# Adapter-TenX-CurrentSink.net
KiCad netlist of a schematic drawn in EAGLE
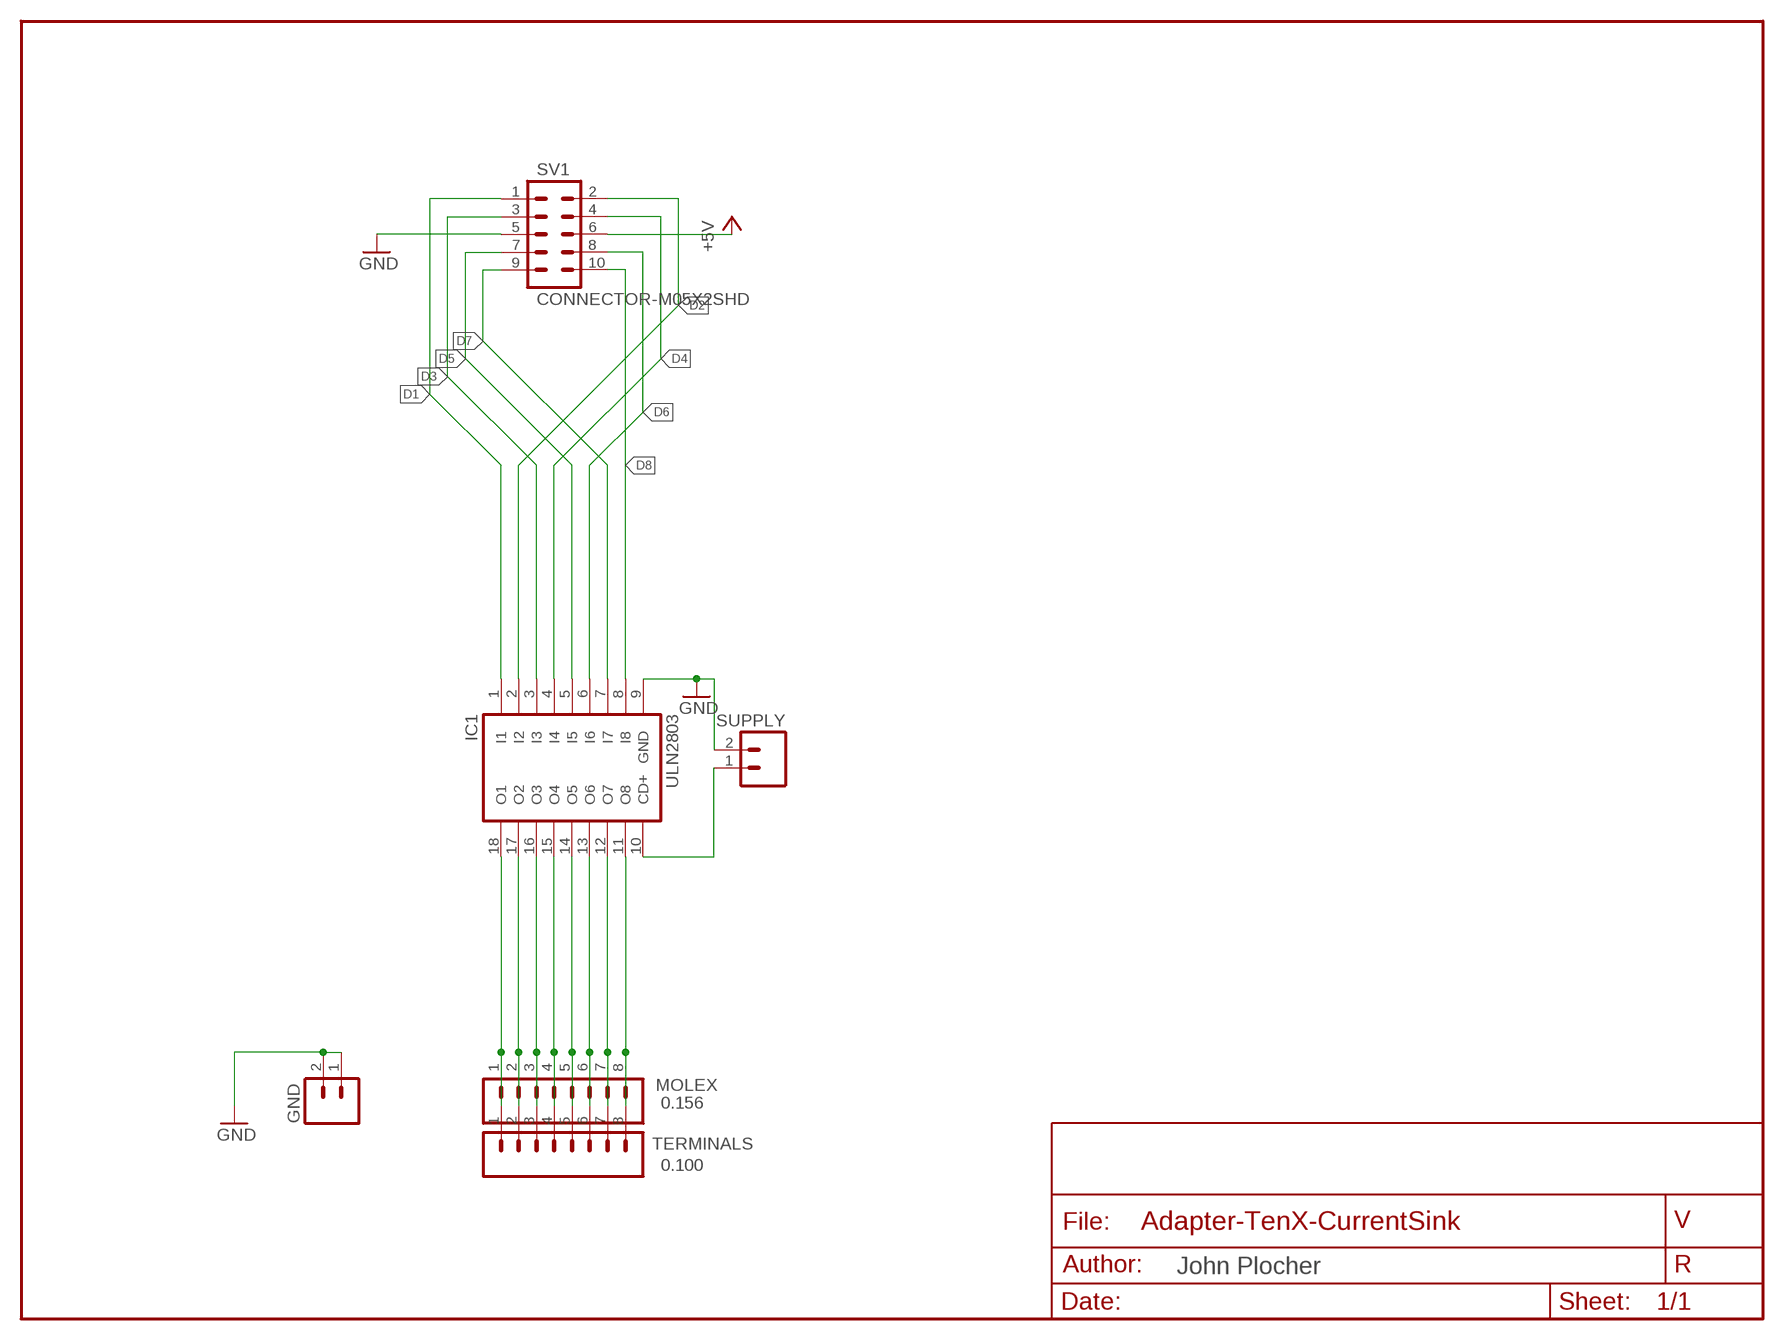
[diagram p0: schematic, sheet 1]

(export (version "E")
  (design (tool "Eeschema 10.0.6"))
  (components
    (comp (ref "GND")
      (value "M02POLAR_LOCK")
      (footprint "eagle-import:MOLEX-1X2_LOCK")
      (libsource (lib "eagle-import") (part "M02POLAR_LOCK"))
    )
    (comp (ref "IC1")
      (value "ULN2803")
      (footprint "eagle-import:DIL18")
      (libsource (lib "eagle-import") (part "ULN2803A"))
    )
    (comp (ref "MOLEX")
      (value "0.156")
      (footprint "eagle-import:KK-156-8-M")
      (libsource (lib "eagle-import") (part "CONNECTOR-M081.56-M"))
    )
    (comp (ref "SUPPLY")
      (value "M02POLAR_LOCK")
      (footprint "eagle-import:MOLEX-1X2_LOCK")
      (libsource (lib "eagle-import") (part "M02POLAR_LOCK"))
    )
    (comp (ref "SV1")
      (value "CONNECTOR-M05X2SHD")
      (footprint "eagle-import:2X5-SHROUDED")
      (libsource (lib "eagle-import") (part "CONNECTOR-M05X2SHD"))
    )
    (comp (ref "TERMINALS")
      (value "0.100")
      (footprint "eagle-import:1X08_LOCK_LONGPADS")
      (libsource (lib "eagle-import") (part "CONNECTOR-M08LOCK_LONGPADS"))
    )
  )
  (nets
    (net (code "1") (name "+5V") (class "Default")
      (node (ref "SV1") (pin "6") (pinfunction "6_6") (pintype "passive"))
    )
    (net (code "2") (name "D1") (class "Default")
      (node (ref "IC1") (pin "1") (pinfunction "I1_1") (pintype "input"))
      (node (ref "SV1") (pin "1") (pinfunction "1_1") (pintype "passive"))
    )
    (net (code "3") (name "D2") (class "Default")
      (node (ref "IC1") (pin "2") (pinfunction "I2_2") (pintype "input"))
      (node (ref "SV1") (pin "2") (pinfunction "2_2") (pintype "passive"))
    )
    (net (code "4") (name "D3") (class "Default")
      (node (ref "IC1") (pin "3") (pinfunction "I3_3") (pintype "input"))
      (node (ref "SV1") (pin "3") (pinfunction "3_3") (pintype "passive"))
    )
    (net (code "5") (name "D4") (class "Default")
      (node (ref "IC1") (pin "4") (pinfunction "I4_4") (pintype "input"))
      (node (ref "SV1") (pin "4") (pinfunction "4_4") (pintype "passive"))
    )
    (net (code "6") (name "D5") (class "Default")
      (node (ref "IC1") (pin "5") (pinfunction "I5_5") (pintype "input"))
      (node (ref "SV1") (pin "7") (pinfunction "7_7") (pintype "passive"))
    )
    (net (code "7") (name "D6") (class "Default")
      (node (ref "IC1") (pin "6") (pinfunction "I6_6") (pintype "input"))
      (node (ref "SV1") (pin "8") (pinfunction "8_8") (pintype "passive"))
    )
    (net (code "8") (name "D7") (class "Default")
      (node (ref "IC1") (pin "7") (pinfunction "I7_7") (pintype "input"))
      (node (ref "SV1") (pin "9") (pinfunction "9_9") (pintype "passive"))
    )
    (net (code "9") (name "D8") (class "Default")
      (node (ref "IC1") (pin "8") (pinfunction "I8_8") (pintype "input"))
      (node (ref "SV1") (pin "10") (pinfunction "10_10") (pintype "passive"))
    )
    (net (code "10") (name "GND") (class "Default")
      (node (ref "GND") (pin "1") (pinfunction "1_1") (pintype "passive"))
      (node (ref "GND") (pin "2") (pinfunction "2_2") (pintype "passive"))
      (node (ref "IC1") (pin "9") (pinfunction "GND_9") (pintype "power_in"))
      (node (ref "SUPPLY") (pin "2") (pinfunction "2_2") (pintype "passive"))
      (node (ref "SV1") (pin "5") (pinfunction "5_5") (pintype "passive"))
    )
    (net (code "11") (name "Net-(IC1-CD+)") (class "Default")
      (node (ref "IC1") (pin "10") (pinfunction "CD+_10") (pintype "passive"))
      (node (ref "SUPPLY") (pin "1") (pinfunction "1_1") (pintype "passive"))
    )
    (net (code "12") (name "Net-(IC1-O1)") (class "Default")
      (node (ref "IC1") (pin "18") (pinfunction "O1_18") (pintype "open_collector"))
      (node (ref "MOLEX") (pin "1") (pinfunction "1_1") (pintype "passive"))
      (node (ref "TERMINALS") (pin "1") (pinfunction "1_1") (pintype "passive"))
    )
    (net (code "13") (name "Net-(IC1-O2)") (class "Default")
      (node (ref "IC1") (pin "17") (pinfunction "O2_17") (pintype "open_collector"))
      (node (ref "MOLEX") (pin "2") (pinfunction "2_2") (pintype "passive"))
      (node (ref "TERMINALS") (pin "2") (pinfunction "2_2") (pintype "passive"))
    )
    (net (code "14") (name "Net-(IC1-O3)") (class "Default")
      (node (ref "IC1") (pin "16") (pinfunction "O3_16") (pintype "open_collector"))
      (node (ref "MOLEX") (pin "3") (pinfunction "3_3") (pintype "passive"))
      (node (ref "TERMINALS") (pin "3") (pinfunction "3_3") (pintype "passive"))
    )
    (net (code "15") (name "Net-(IC1-O4)") (class "Default")
      (node (ref "IC1") (pin "15") (pinfunction "O4_15") (pintype "open_collector"))
      (node (ref "MOLEX") (pin "4") (pinfunction "4_4") (pintype "passive"))
      (node (ref "TERMINALS") (pin "4") (pinfunction "4_4") (pintype "passive"))
    )
    (net (code "16") (name "Net-(IC1-O5)") (class "Default")
      (node (ref "IC1") (pin "14") (pinfunction "O5_14") (pintype "open_collector"))
      (node (ref "MOLEX") (pin "5") (pinfunction "5_5") (pintype "passive"))
      (node (ref "TERMINALS") (pin "5") (pinfunction "5_5") (pintype "passive"))
    )
    (net (code "17") (name "Net-(IC1-O6)") (class "Default")
      (node (ref "IC1") (pin "13") (pinfunction "O6_13") (pintype "open_collector"))
      (node (ref "MOLEX") (pin "6") (pinfunction "6_6") (pintype "passive"))
      (node (ref "TERMINALS") (pin "6") (pinfunction "6_6") (pintype "passive"))
    )
    (net (code "18") (name "Net-(IC1-O7)") (class "Default")
      (node (ref "IC1") (pin "12") (pinfunction "O7_12") (pintype "open_collector"))
      (node (ref "MOLEX") (pin "7") (pinfunction "7_7") (pintype "passive"))
      (node (ref "TERMINALS") (pin "7") (pinfunction "7_7") (pintype "passive"))
    )
    (net (code "19") (name "Net-(IC1-O8)") (class "Default")
      (node (ref "IC1") (pin "11") (pinfunction "O8_11") (pintype "open_collector"))
      (node (ref "MOLEX") (pin "8") (pinfunction "8_8") (pintype "passive"))
      (node (ref "TERMINALS") (pin "8") (pinfunction "8_8") (pintype "passive"))
    )
  )
)
